# thermocoupleMv2.net
KiCad netlist of a schematic drawn in EAGLE
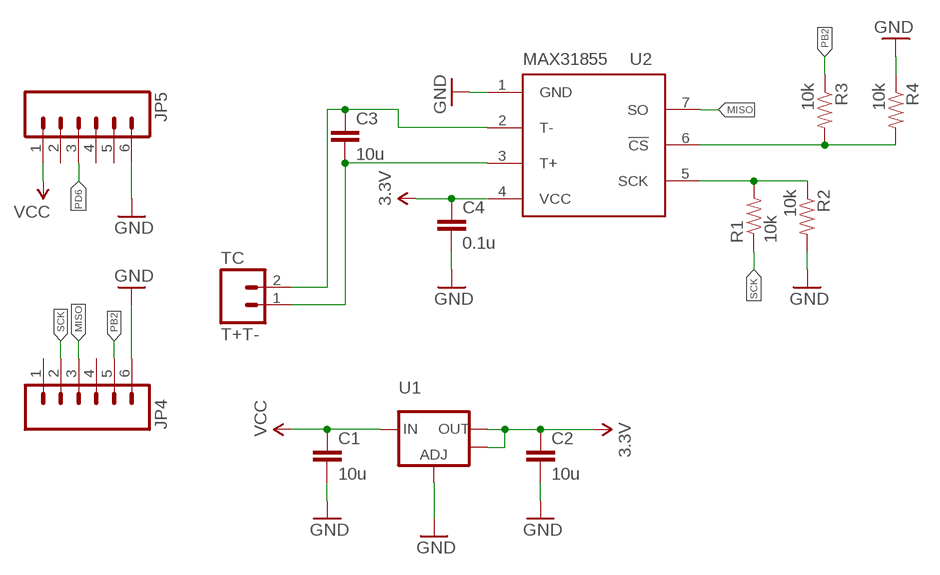
[diagram p0: schematic, sheet 1]

(export (version "E")
  (design (tool "Eeschema 10.0.6"))
  (components
    (comp (ref "C1")
      (value "10u")
      (footprint "eagle-import:0805")
      (libsource (lib "eagle-import") (part "CAP0805"))
    )
    (comp (ref "C2")
      (value "10u")
      (footprint "eagle-import:0805")
      (libsource (lib "eagle-import") (part "CAP0805"))
    )
    (comp (ref "C3")
      (value "10u")
      (footprint "eagle-import:0805")
      (libsource (lib "eagle-import") (part "CAP0805"))
    )
    (comp (ref "C4")
      (value "0.1u")
      (footprint "eagle-import:0805")
      (libsource (lib "eagle-import") (part "CAP0805"))
    )
    (comp (ref "JP4")
      (value "M06LOCK_LONGPADS")
      (footprint "eagle-import:1X06_LOCK_LONGPADS")
      (libsource (lib "eagle-import") (part "M06LOCK_LONGPADS"))
    )
    (comp (ref "JP5")
      (value "M06LOCK_LONGPADS")
      (footprint "eagle-import:1X06_LOCK_LONGPADS")
      (libsource (lib "eagle-import") (part "M06LOCK_LONGPADS"))
    )
    (comp (ref "R1")
      (value "10k")
      (footprint "eagle-import:0805")
      (libsource (lib "eagle-import") (part "RESISTOR0805-RES"))
    )
    (comp (ref "R2")
      (value "10k")
      (footprint "eagle-import:0805")
      (libsource (lib "eagle-import") (part "RESISTOR0805-RES"))
    )
    (comp (ref "R3")
      (value "10k")
      (footprint "eagle-import:0805")
      (libsource (lib "eagle-import") (part "RESISTOR0805-RES"))
    )
    (comp (ref "R4")
      (value "10k")
      (footprint "eagle-import:0805")
      (libsource (lib "eagle-import") (part "RESISTOR0805-RES"))
    )
    (comp (ref "TC")
      (value "T+T-")
      (footprint "eagle-import:1X02_LOCK_LONGPADS")
      (libsource (lib "eagle-import") (part "M02LOCK_LONGPADS"))
    )
    (comp (ref "U1")
      (value "V_REG_LM1117SOT223")
      (footprint "eagle-import:SOT223")
      (libsource (lib "eagle-import") (part "V_REG_LM1117SOT223"))
    )
    (comp (ref "U2")
      (value "MAX31855")
      (footprint "eagle-import:SO08")
      (libsource (lib "eagle-import") (part "MAX6675"))
    )
  )
  (nets
    (net (code "1") (name "3.3V") (class "Default")
      (node (ref "C2") (pin "1") (pinfunction "1_1") (pintype "passive"))
      (node (ref "C4") (pin "1") (pinfunction "1_1") (pintype "passive"))
      (node (ref "U1") (pin "2") (pinfunction "OUT_2") (pintype "output"))
      (node (ref "U1") (pin "4") (pinfunction "OUT_4") (pintype "output"))
      (node (ref "U2") (pin "4") (pinfunction "VCC_4") (pintype "bidirectional"))
    )
    (net (code "2") (name "GND") (class "Default")
      (node (ref "C1") (pin "2") (pinfunction "2_2") (pintype "passive"))
      (node (ref "C2") (pin "2") (pinfunction "2_2") (pintype "passive"))
      (node (ref "C4") (pin "2") (pinfunction "2_2") (pintype "passive"))
      (node (ref "JP4") (pin "6") (pinfunction "6_6") (pintype "passive"))
      (node (ref "JP5") (pin "6") (pinfunction "6_6") (pintype "passive"))
      (node (ref "R2") (pin "2") (pinfunction "2_2") (pintype "passive"))
      (node (ref "R4") (pin "1") (pinfunction "1_1") (pintype "passive"))
      (node (ref "U1") (pin "1") (pinfunction "ADJ_1") (pintype "input"))
      (node (ref "U2") (pin "1") (pinfunction "GND_1") (pintype "bidirectional"))
    )
    (net (code "3") (name "MISO") (class "Default")
      (node (ref "JP4") (pin "3") (pinfunction "3_3") (pintype "passive"))
      (node (ref "U2") (pin "7") (pinfunction "SO_7") (pintype "bidirectional"))
    )
    (net (code "4") (name "Net-(U2-SCK)") (class "Default")
      (node (ref "R1") (pin "2") (pinfunction "2_2") (pintype "passive"))
      (node (ref "R2") (pin "1") (pinfunction "1_1") (pintype "passive"))
      (node (ref "U2") (pin "5") (pinfunction "SCK_5") (pintype "bidirectional"))
    )
    (net (code "5") (name "Net-(U2-T+)") (class "Default")
      (node (ref "C3") (pin "2") (pinfunction "2_2") (pintype "passive"))
      (node (ref "TC") (pin "1") (pinfunction "1_1") (pintype "passive"))
      (node (ref "U2") (pin "3") (pinfunction "T+_3") (pintype "bidirectional"))
    )
    (net (code "6") (name "Net-(U2-T-)") (class "Default")
      (node (ref "C3") (pin "1") (pinfunction "1_1") (pintype "passive"))
      (node (ref "TC") (pin "2") (pinfunction "2_2") (pintype "passive"))
      (node (ref "U2") (pin "2") (pinfunction "T-_2") (pintype "bidirectional"))
    )
    (net (code "7") (name "Net-(U2-~{CS})") (class "Default")
      (node (ref "R3") (pin "2") (pinfunction "2_2") (pintype "passive"))
      (node (ref "R4") (pin "2") (pinfunction "2_2") (pintype "passive"))
      (node (ref "U2") (pin "6") (pinfunction "~{CS}_6") (pintype "bidirectional"))
    )
    (net (code "8") (name "PB2") (class "Default")
      (node (ref "JP4") (pin "5") (pinfunction "5_5") (pintype "passive"))
      (node (ref "R3") (pin "1") (pinfunction "1_1") (pintype "passive"))
    )
    (net (code "9") (name "PD6") (class "Default")
      (node (ref "JP5") (pin "3") (pinfunction "3_3") (pintype "passive"))
    )
    (net (code "10") (name "SCK") (class "Default")
      (node (ref "JP4") (pin "2") (pinfunction "2_2") (pintype "passive"))
      (node (ref "R1") (pin "1") (pinfunction "1_1") (pintype "passive"))
    )
    (net (code "11") (name "VCC") (class "Default")
      (node (ref "C1") (pin "1") (pinfunction "1_1") (pintype "passive"))
      (node (ref "JP5") (pin "1") (pinfunction "1_1") (pintype "passive"))
      (node (ref "U1") (pin "3") (pinfunction "IN_3") (pintype "input"))
    )
    (net (code "12") (name "unconnected-(JP4-Pad1)") (class "Default")
      (node (ref "JP4") (pin "1") (pinfunction "1_1") (pintype "passive"))
    )
    (net (code "13") (name "unconnected-(JP4-Pad4)") (class "Default")
      (node (ref "JP4") (pin "4") (pinfunction "4_4") (pintype "passive"))
    )
    (net (code "14") (name "unconnected-(JP5-Pad2)") (class "Default")
      (node (ref "JP5") (pin "2") (pinfunction "2_2") (pintype "passive"))
    )
    (net (code "15") (name "unconnected-(JP5-Pad4)") (class "Default")
      (node (ref "JP5") (pin "4") (pinfunction "4_4") (pintype "passive"))
    )
    (net (code "16") (name "unconnected-(JP5-Pad5)") (class "Default")
      (node (ref "JP5") (pin "5") (pinfunction "5_5") (pintype "passive"))
    )
  )
)
